# tritiled22_lux_z.net
KiCad netlist of a schematic drawn in EAGLE
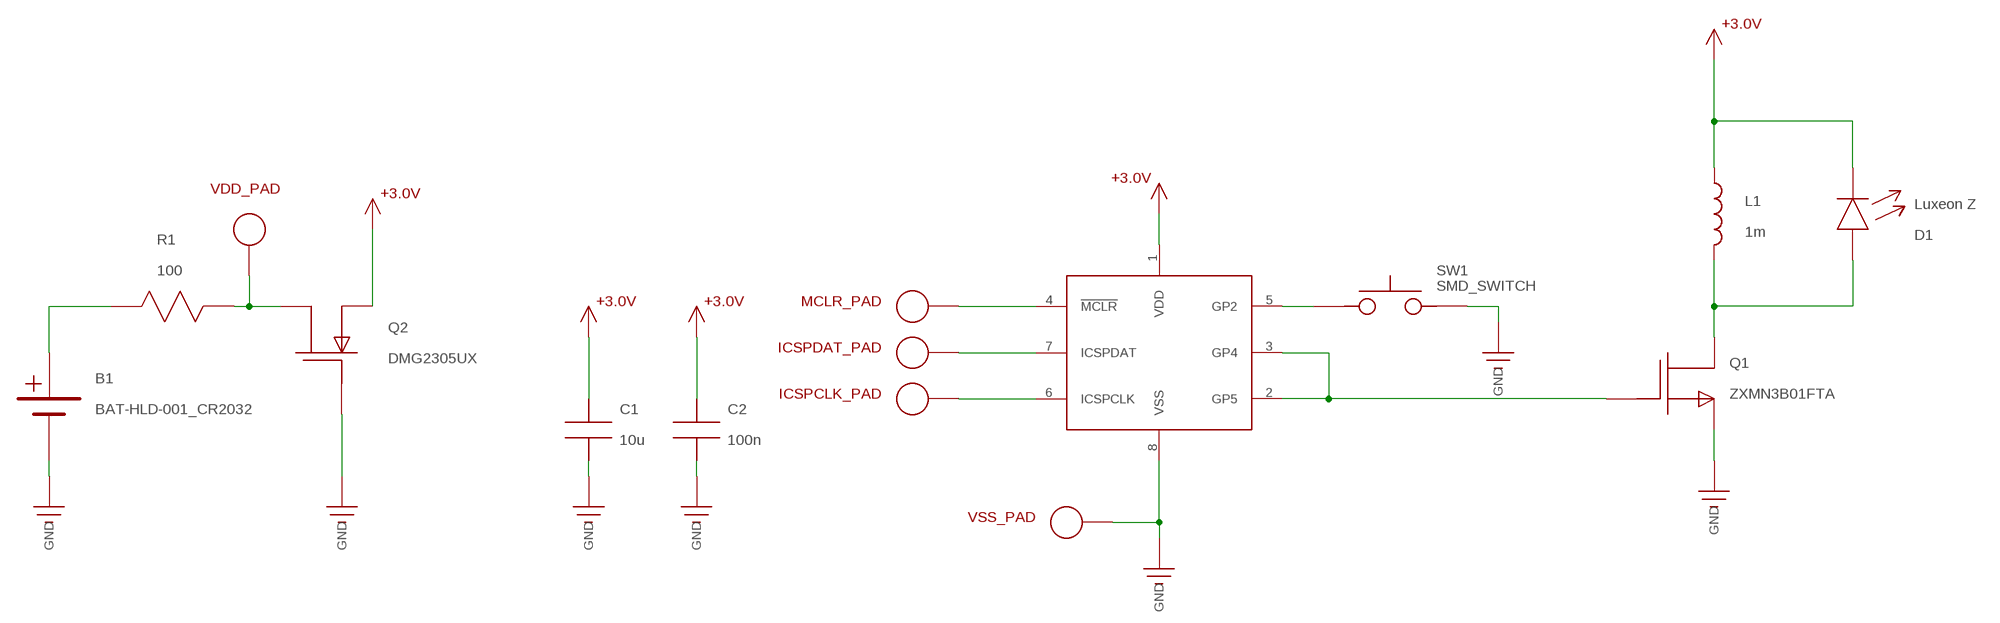
[diagram p0: schematic, sheet 1]

(export (version "E")
  (design (tool "Eeschema 10.0.6"))
  (components
    (comp (ref "B1")
      (value "BAT-HLD-001_CR2032")
      (footprint "eagle-import:CR2032_BAT-HLD_001")
      (libsource (lib "eagle-import") (part "BAT-HLD-001_CR2032"))
    )
    (comp (ref "C1")
      (value "10u")
      (footprint "eagle-import:1206")
      (libsource (lib "eagle-import") (part "C1206"))
    )
    (comp (ref "C2")
      (value "100n")
      (footprint "eagle-import:0805")
      (libsource (lib "eagle-import") (part "C0805"))
    )
    (comp (ref "D1")
      (value "Luxeon Z")
      (footprint "eagle-import:LUXEON_Z")
      (libsource (lib "eagle-import") (part "LEDLUXEON_Z"))
    )
    (comp (ref "ICSPCLK_PAD")
      (value "ICSP_PAD")
      (footprint "eagle-import:ICSP_PAD")
      (libsource (lib "eagle-import") (part "ICSP_PAD"))
    )
    (comp (ref "ICSPDAT_PAD")
      (value "ICSP_PAD")
      (footprint "eagle-import:ICSP_PAD")
      (libsource (lib "eagle-import") (part "ICSP_PAD"))
    )
    (comp (ref "L1")
      (value "1m")
      (footprint "eagle-import:SRR6028_INDUCTOR")
      (libsource (lib "eagle-import") (part "SRR6028_INDUCTOR"))
    )
    (comp (ref "MCLR_PAD")
      (value "ICSP_PAD")
      (footprint "eagle-import:ICSP_PAD")
      (libsource (lib "eagle-import") (part "ICSP_PAD"))
    )
    (comp (ref "Q1")
      (value "ZXMN3B01FTA")
      (footprint "eagle-import:SOT-23")
      (libsource (lib "eagle-import") (part "ZXMN3B01FSOT23"))
    )
    (comp (ref "Q2")
      (value "DMG2305UX")
      (footprint "eagle-import:SOT-23")
      (libsource (lib "eagle-import") (part "DMG2305UXSOT23"))
    )
    (comp (ref "R1")
      (value "100")
      (footprint "eagle-import:R1206")
      (libsource (lib "eagle-import") (part "R1206"))
    )
    (comp (ref "SW1")
      (value "SMD_SWITCH")
      (footprint "eagle-import:SMD_SWITCH")
      (libsource (lib "eagle-import") (part "SMD_SWITCH"))
    )
    (comp (ref "U1")
      (value "PIC12LF1571")
      (footprint "eagle-import:SOIC8")
      (libsource (lib "eagle-import") (part "PIC12LF1571"))
    )
    (comp (ref "VDD_PAD")
      (value "ICSP_PAD")
      (footprint "eagle-import:ICSP_PAD")
      (libsource (lib "eagle-import") (part "ICSP_PAD"))
    )
    (comp (ref "VSS_PAD")
      (value "ICSP_PAD")
      (footprint "eagle-import:ICSP_PAD")
      (libsource (lib "eagle-import") (part "ICSP_PAD"))
    )
  )
  (nets
    (net (code "1") (name "+3.0V") (class "Default")
      (node (ref "C1") (pin "P$1") (pinfunction "P$1_P$1") (pintype "bidirectional"))
      (node (ref "C2") (pin "P$1") (pinfunction "P$1_P$1") (pintype "bidirectional"))
      (node (ref "D1") (pin "C") (pinfunction "C_C") (pintype "bidirectional"))
      (node (ref "L1") (pin "P$1") (pinfunction "1_P$1") (pintype "passive"))
      (node (ref "Q2") (pin "2") (pinfunction "S_2") (pintype "bidirectional"))
      (node (ref "U1") (pin "1") (pinfunction "VDD_1") (pintype "bidirectional"))
    )
    (net (code "2") (name "GND") (class "Default")
      (node (ref "B1") (pin "GND") (pinfunction "0V_GND") (pintype "power_in"))
      (node (ref "C1") (pin "P$2") (pinfunction "P$2_P$2") (pintype "bidirectional"))
      (node (ref "C2") (pin "P$2") (pinfunction "P$2_P$2") (pintype "bidirectional"))
      (node (ref "Q1") (pin "2") (pinfunction "S_2") (pintype "bidirectional"))
      (node (ref "Q2") (pin "1") (pinfunction "G_1") (pintype "bidirectional"))
      (node (ref "SW1") (pin "P$3") (pinfunction "P$2_P$3") (pintype "bidirectional"))
      (node (ref "SW1") (pin "P$4") (pinfunction "P$2_P$4") (pintype "bidirectional"))
      (node (ref "U1") (pin "8") (pinfunction "VSS_8") (pintype "bidirectional"))
      (node (ref "VSS_PAD") (pin "P$2") (pinfunction "P$1_P$2") (pintype "bidirectional"))
    )
    (net (code "3") (name "Net-(B1-+V-Pad+V1)") (class "Default")
      (node (ref "B1") (pin "+V1") (pinfunction "+V_+V1") (pintype "power_in"))
      (node (ref "B1") (pin "+V2") (pinfunction "+V_+V2") (pintype "power_in"))
      (node (ref "R1") (pin "P$1") (pinfunction "P$1_P$1") (pintype "bidirectional"))
    )
    (net (code "4") (name "Net-(ICSPCLK_PAD-P$1)") (class "Default")
      (node (ref "ICSPCLK_PAD") (pin "P$2") (pinfunction "P$1_P$2") (pintype "bidirectional"))
      (node (ref "U1") (pin "6") (pinfunction "ICSPCLK_6") (pintype "bidirectional"))
    )
    (net (code "5") (name "Net-(ICSPDAT_PAD-P$1)") (class "Default")
      (node (ref "ICSPDAT_PAD") (pin "P$2") (pinfunction "P$1_P$2") (pintype "bidirectional"))
      (node (ref "U1") (pin "7") (pinfunction "ICSPDAT_7") (pintype "bidirectional"))
    )
    (net (code "6") (name "Net-(L1-2)") (class "Default")
      (node (ref "D1") (pin "A") (pinfunction "A_A") (pintype "bidirectional"))
      (node (ref "L1") (pin "P$2") (pinfunction "2_P$2") (pintype "passive"))
      (node (ref "Q1") (pin "3") (pinfunction "D_3") (pintype "bidirectional"))
    )
    (net (code "7") (name "Net-(MCLR_PAD-P$1)") (class "Default")
      (node (ref "MCLR_PAD") (pin "P$2") (pinfunction "P$1_P$2") (pintype "bidirectional"))
      (node (ref "U1") (pin "4") (pinfunction "~{MCLR}_4") (pintype "bidirectional"))
    )
    (net (code "8") (name "Net-(Q1-G)") (class "Default")
      (node (ref "Q1") (pin "1") (pinfunction "G_1") (pintype "bidirectional"))
      (node (ref "U1") (pin "2") (pinfunction "GP5_2") (pintype "bidirectional"))
      (node (ref "U1") (pin "3") (pinfunction "GP4_3") (pintype "bidirectional"))
    )
    (net (code "9") (name "Net-(Q2-D)") (class "Default")
      (node (ref "Q2") (pin "3") (pinfunction "D_3") (pintype "bidirectional"))
      (node (ref "R1") (pin "P$2") (pinfunction "P$2_P$2") (pintype "bidirectional"))
      (node (ref "VDD_PAD") (pin "P$2") (pinfunction "P$1_P$2") (pintype "bidirectional"))
    )
    (net (code "10") (name "Net-(U1-GP2)") (class "Default")
      (node (ref "SW1") (pin "P$1") (pinfunction "P$1_P$1") (pintype "bidirectional"))
      (node (ref "SW1") (pin "P$2") (pinfunction "P$1_P$2") (pintype "bidirectional"))
      (node (ref "U1") (pin "5") (pinfunction "GP2_5") (pintype "bidirectional"))
    )
  )
)
